# RADIO_nRF24L01.net
KiCad netlist of a schematic drawn in Altium Designer
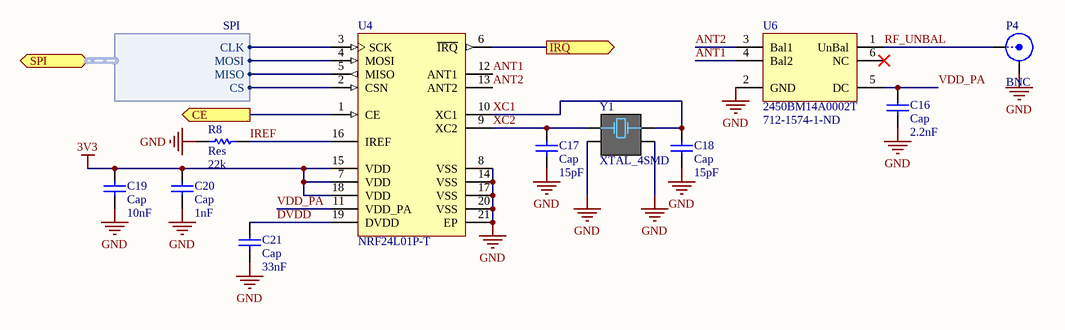
[diagram p0: RADIO_nRF24L01.SchDoc]

(export (version "E")
  (design (tool "Eeschema 10.0.6"))
  (components
    (comp (ref "C16")
      (value "Cap")
      (footprint "CAPC1005N")
      (description "Capacitor")
      (fields (field (name "ALTIUM_VALUE") "2.2nF") (field (name "PUBLISHER") "Altium Limited"))
      (libsource (lib "Miscellaneous Devices") (part "Cap"))
    )
    (comp (ref "C17")
      (value "Cap")
      (footprint "CAPC1005N")
      (description "Capacitor")
      (fields (field (name "ALTIUM_VALUE") "15pF") (field (name "PUBLISHER") "Altium Limited"))
      (libsource (lib "Miscellaneous Devices") (part "Cap"))
    )
    (comp (ref "C18")
      (value "Cap")
      (footprint "CAPC1005N")
      (description "Capacitor")
      (fields (field (name "ALTIUM_VALUE") "15pF") (field (name "PUBLISHER") "Altium Limited"))
      (libsource (lib "Miscellaneous Devices") (part "Cap"))
    )
    (comp (ref "C19")
      (value "Cap")
      (footprint "CAPC1005N")
      (description "Capacitor")
      (fields (field (name "ALTIUM_VALUE") "10nF") (field (name "PUBLISHER") "Altium Limited"))
      (libsource (lib "Miscellaneous Devices") (part "Cap"))
    )
    (comp (ref "C20")
      (value "Cap")
      (footprint "CAPC1005N")
      (description "Capacitor")
      (fields (field (name "ALTIUM_VALUE") "1nF") (field (name "PUBLISHER") "Altium Limited"))
      (libsource (lib "Miscellaneous Devices") (part "Cap"))
    )
    (comp (ref "C21")
      (value "Cap")
      (footprint "CAPC1005N")
      (description "Capacitor")
      (fields (field (name "ALTIUM_VALUE") "33nF") (field (name "PUBLISHER") "Altium Limited"))
      (libsource (lib "Miscellaneous Devices") (part "Cap"))
    )
    (comp (ref "P4")
      (value "BNC")
      (footprint "MCB3-V4")
      (description "BNC Elbow Connector")
      (fields (field (name "PUBLISHER") "Altium Limited"))
      (libsource (lib "Miscellaneous Connectors") (part "BNC"))
    )
    (comp (ref "R8")
      (value "Res")
      (footprint "RESC1005N")
      (description "Resistor")
      (fields (field (name "ALTIUM_VALUE") "22k") (field (name "PUBLISHER") "Altium Limited"))
      (libsource (lib "Miscellaneous Devices") (part "Res1"))
    )
    (comp (ref "U4")
      (value "NRF24L01P-T")
      (footprint "NRSC-QFN-20_L")
      (description "Single Chip Transceiver, 2.4 GHz, 60 mW, 1.9 to 3.6 V, -40 to 85 degC, 20-Pin QFN, RoHS, Tray")
      (fields (field (name "MANUFACTURER") "Nordic Semiconductor"))
      (libsource (lib "Components - 28.10.19 - 20.35") (part "CMP-2000-06859-1"))
    )
    (comp (ref "U6")
      (value "2450BM14A0002T")
      (footprint "2450BM14A0002")
      (description "JOHANSON TECHNOLOGY - 2450BM14A0002T - BALUN, 2.45GHZ, IMPEDANCE MATCHED")
      (fields (field (name "SUPPLIER PART NUMBER 1") "712-1574-1-ND"))
      (libsource (lib "Schlib1") (part "2450BM14A0002T"))
    )
    (comp (ref "Y1")
      (value "XTAL_4SMD")
      (footprint "XTAL3225-4-N")
      (description "Crystal Oscillator (4 pin)")
      (fields (field (name "PUBLISHER") "Altium Limited"))
      (libsource (lib "Miscellaneous Devices") (part "XTAL_4SMD"))
    )
  )
  (nets
    (net (code "2") (name "/ANT1") (class "Default")
      (node (ref "U4") (pin "12") (pinfunction "ANT1_12") (pintype "passive"))
      (node (ref "U6") (pin "4") (pinfunction "Bal2_4") (pintype "passive"))
    )
    (net (code "3") (name "/ANT2") (class "Default")
      (node (ref "U4") (pin "13") (pinfunction "ANT2_13") (pintype "passive"))
      (node (ref "U6") (pin "3") (pinfunction "Bal1_3") (pintype "passive"))
    )
    (net (code "4") (name "/CE") (class "Default")
      (node (ref "U4") (pin "1") (pinfunction "CE_1") (pintype "input"))
    )
    (net (code "5") (name "/CLK") (class "Default")
      (node (ref "U4") (pin "3") (pinfunction "SCK_3") (pintype "input"))
    )
    (net (code "6") (name "/CS") (class "Default")
      (node (ref "U4") (pin "2") (pinfunction "CSN_2") (pintype "input"))
    )
    (net (code "7") (name "/DVDD") (class "Default")
      (node (ref "C21") (pin "2") (pinfunction "2_2") (pintype "passive"))
      (node (ref "U4") (pin "19") (pinfunction "DVDD_19") (pintype "power_in"))
    )
    (net (code "8") (name "/IREF") (class "Default")
      (node (ref "R8") (pin "2") (pinfunction "2_2") (pintype "passive"))
      (node (ref "U4") (pin "16") (pinfunction "IREF_16") (pintype "passive"))
    )
    (net (code "9") (name "/IRQ") (class "Default")
      (node (ref "U4") (pin "6") (pinfunction "~{IRQ}_6") (pintype "output"))
    )
    (net (code "10") (name "/MISO") (class "Default")
      (node (ref "U4") (pin "5") (pinfunction "MISO_5") (pintype "output"))
    )
    (net (code "11") (name "/MOSI") (class "Default")
      (node (ref "U4") (pin "4") (pinfunction "MOSI_4") (pintype "input"))
    )
    (net (code "12") (name "/RF_UNBAL") (class "Default")
      (node (ref "P4") (pin "1") (pinfunction "X_1") (pintype "passive"))
      (node (ref "U6") (pin "1") (pinfunction "UnBal_1") (pintype "passive"))
    )
    (net (code "13") (name "/VDD_PA") (class "Default")
      (node (ref "C16") (pin "2") (pinfunction "2_2") (pintype "passive"))
      (node (ref "U4") (pin "11") (pinfunction "VDD_PA_11") (pintype "power_in"))
      (node (ref "U6") (pin "5") (pinfunction "DC_5") (pintype "passive"))
    )
    (net (code "14") (name "/XC1") (class "Default")
      (node (ref "C18") (pin "2") (pinfunction "2_2") (pintype "passive"))
      (node (ref "U4") (pin "10") (pinfunction "XC1_10") (pintype "passive"))
      (node (ref "Y1") (pin "3") (pinfunction "OSC2_3") (pintype "passive"))
    )
    (net (code "15") (name "/XC2") (class "Default")
      (node (ref "C17") (pin "2") (pinfunction "2_2") (pintype "passive"))
      (node (ref "U4") (pin "9") (pinfunction "XC2_9") (pintype "passive"))
      (node (ref "Y1") (pin "1") (pinfunction "OSC1_1") (pintype "passive"))
    )
    (net (code "17") (name "3V3") (class "Default")
      (node (ref "C19") (pin "2") (pinfunction "2_2") (pintype "passive"))
      (node (ref "C20") (pin "2") (pinfunction "2_2") (pintype "passive"))
      (node (ref "U4") (pin "15") (pinfunction "VDD_15") (pintype "power_in"))
      (node (ref "U4") (pin "18") (pinfunction "VDD_18") (pintype "power_in"))
      (node (ref "U4") (pin "7") (pinfunction "VDD_7") (pintype "power_in"))
    )
    (net (code "18") (name "GND") (class "Default")
      (node (ref "C16") (pin "1") (pinfunction "1_1") (pintype "passive"))
      (node (ref "C17") (pin "1") (pinfunction "1_1") (pintype "passive"))
      (node (ref "C18") (pin "1") (pinfunction "1_1") (pintype "passive"))
      (node (ref "C19") (pin "1") (pinfunction "1_1") (pintype "passive"))
      (node (ref "C20") (pin "1") (pinfunction "1_1") (pintype "passive"))
      (node (ref "C21") (pin "1") (pinfunction "1_1") (pintype "passive"))
      (node (ref "P4") (pin "2") (pinfunction "Y_2") (pintype "passive"))
      (node (ref "R8") (pin "1") (pinfunction "1_1") (pintype "passive"))
      (node (ref "U4") (pin "14") (pinfunction "VSS_14") (pintype "power_in"))
      (node (ref "U4") (pin "17") (pinfunction "VSS_17") (pintype "power_in"))
      (node (ref "U4") (pin "20") (pinfunction "VSS_20") (pintype "power_in"))
      (node (ref "U4") (pin "21") (pinfunction "EP_21") (pintype "passive"))
      (node (ref "U4") (pin "8") (pinfunction "VSS_8") (pintype "power_in"))
      (node (ref "U6") (pin "2") (pinfunction "GND_2") (pintype "passive"))
      (node (ref "Y1") (pin "2") (pinfunction "2_2") (pintype "power_in"))
      (node (ref "Y1") (pin "4") (pinfunction "4_4") (pintype "power_in"))
    )
    (net (code "19") (name "unconnected-(U6-NC-Pad6)") (class "Default")
      (node (ref "U6") (pin "6") (pinfunction "NC_6") (pintype "passive+no_connect"))
    )
  )
)
